# servox6-2sch.net
KiCad netlist of a schematic drawn in EAGLE
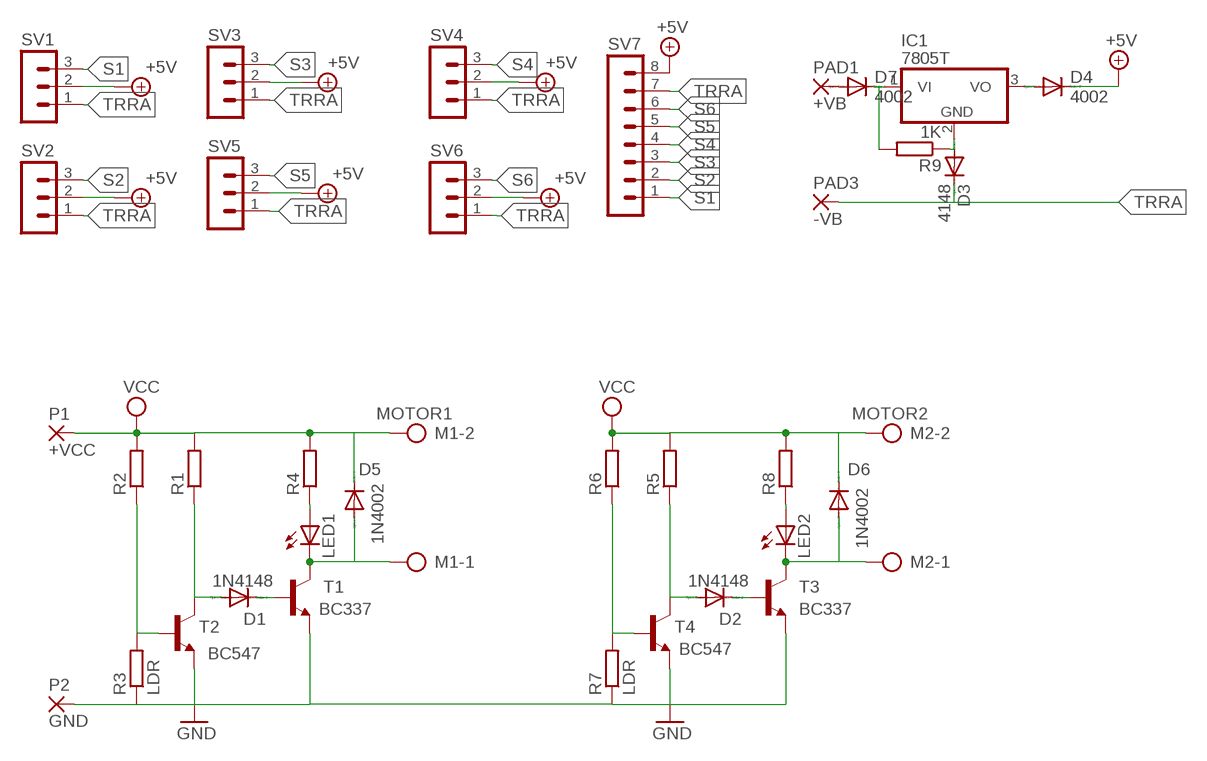
[diagram p0: schematic, sheet 1]

(export (version "E")
  (design (tool "Eeschema 10.0.6"))
  (components
    (comp (ref "D1")
      (value "1N4148")
      (footprint "eagle-import:DO35-7")
      (libsource (lib "eagle-import") (part "1N4148DO35-7"))
    )
    (comp (ref "D2")
      (value "1N4148")
      (footprint "eagle-import:DO35-7")
      (libsource (lib "eagle-import") (part "1N4148DO35-7"))
    )
    (comp (ref "D3")
      (value "4148")
      (footprint "eagle-import:DO35-7")
      (libsource (lib "eagle-import") (part "1N4148DO35-7"))
    )
    (comp (ref "D4")
      (value "4002")
      (footprint "eagle-import:DO35-7")
      (libsource (lib "eagle-import") (part "1N4148DO35-7"))
    )
    (comp (ref "D5")
      (value "1N4002")
      (footprint "eagle-import:DO41-10")
      (libsource (lib "eagle-import") (part "1N4933"))
    )
    (comp (ref "D6")
      (value "1N4002")
      (footprint "eagle-import:DO41-10")
      (libsource (lib "eagle-import") (part "1N4933"))
    )
    (comp (ref "D7")
      (value "4002")
      (footprint "eagle-import:DO35-7")
      (libsource (lib "eagle-import") (part "1N4148DO35-7"))
    )
    (comp (ref "IC1")
      (value "7805T")
      (footprint "eagle-import:TO220H")
      (libsource (lib "eagle-import") (part "78T05"))
    )
    (comp (ref "LED1")
      (value "LED3MM")
      (footprint "eagle-import:LED3MM")
      (libsource (lib "eagle-import") (part "LED3MM"))
    )
    (comp (ref "LED2")
      (value "LED3MM")
      (footprint "eagle-import:LED3MM")
      (libsource (lib "eagle-import") (part "LED3MM"))
    )
    (comp (ref "M1")
      (value "MOTOR1")
      (footprint "eagle-import:AK500_2")
      (libsource (lib "eagle-import") (part "AK500/2"))
    )
    (comp (ref "M2")
      (value "MOTOR2")
      (footprint "eagle-import:AK500_2")
      (libsource (lib "eagle-import") (part "AK500/2"))
    )
    (comp (ref "P1")
      (value "+VCC")
      (footprint "eagle-import:2,15_1,0")
      (libsource (lib "eagle-import") (part "WIREPAD2,15/1,0"))
    )
    (comp (ref "P2")
      (value "GND")
      (footprint "eagle-import:2,15_1,0")
      (libsource (lib "eagle-import") (part "WIREPAD2,15/1,0"))
    )
    (comp (ref "PAD1")
      (value "+VB")
      (footprint "eagle-import:1,6_0,9")
      (libsource (lib "eagle-import") (part "WIREPAD1,6/0,9"))
    )
    (comp (ref "PAD3")
      (value "-VB")
      (footprint "eagle-import:1,6_0,9")
      (libsource (lib "eagle-import") (part "WIREPAD1,6/0,9"))
    )
    (comp (ref "R1")
      (value "R-EU_0207/7")
      (footprint "eagle-import:0207_7")
      (libsource (lib "eagle-import") (part "R-EU_0207/7"))
    )
    (comp (ref "R2")
      (value "R-EU_0207/7")
      (footprint "eagle-import:0207_7")
      (libsource (lib "eagle-import") (part "R-EU_0207/7"))
    )
    (comp (ref "R3")
      (value "LDR")
      (footprint "eagle-import:0204_5")
      (libsource (lib "eagle-import") (part "R-EU_0204/5"))
    )
    (comp (ref "R4")
      (value "R-EU_0207/7")
      (footprint "eagle-import:0207_7")
      (libsource (lib "eagle-import") (part "R-EU_0207/7"))
    )
    (comp (ref "R5")
      (value "R-EU_0207/7")
      (footprint "eagle-import:0207_7")
      (libsource (lib "eagle-import") (part "R-EU_0207/7"))
    )
    (comp (ref "R6")
      (value "R-EU_0207/7")
      (footprint "eagle-import:0207_7")
      (libsource (lib "eagle-import") (part "R-EU_0207/7"))
    )
    (comp (ref "R7")
      (value "LDR")
      (footprint "eagle-import:0204_5")
      (libsource (lib "eagle-import") (part "R-EU_0204/5"))
    )
    (comp (ref "R8")
      (value "R-EU_0207/7")
      (footprint "eagle-import:0207_7")
      (libsource (lib "eagle-import") (part "R-EU_0207/7"))
    )
    (comp (ref "R9")
      (value "1K")
      (footprint "eagle-import:0207_7")
      (libsource (lib "eagle-import") (part "R-EU_0207/7"))
    )
    (comp (ref "SV1")
      (value "MA03-1")
      (footprint "eagle-import:MA03-1")
      (libsource (lib "eagle-import") (part "MA03-1"))
    )
    (comp (ref "SV2")
      (value "MA03-1")
      (footprint "eagle-import:MA03-1")
      (libsource (lib "eagle-import") (part "MA03-1"))
    )
    (comp (ref "SV3")
      (value "MA03-1")
      (footprint "eagle-import:MA03-1")
      (libsource (lib "eagle-import") (part "MA03-1"))
    )
    (comp (ref "SV4")
      (value "MA03-1")
      (footprint "eagle-import:MA03-1")
      (libsource (lib "eagle-import") (part "MA03-1"))
    )
    (comp (ref "SV5")
      (value "MA03-1")
      (footprint "eagle-import:MA03-1")
      (libsource (lib "eagle-import") (part "MA03-1"))
    )
    (comp (ref "SV6")
      (value "MA03-1")
      (footprint "eagle-import:MA03-1")
      (libsource (lib "eagle-import") (part "MA03-1"))
    )
    (comp (ref "SV7")
      (value "MA08-1")
      (footprint "eagle-import:MA08-1")
      (libsource (lib "eagle-import") (part "MA08-1"))
    )
    (comp (ref "T1")
      (value "BC337")
      (footprint "eagle-import:TO92-CBE")
      (libsource (lib "eagle-import") (part "-NPN-TO92-CBEBC337-25"))
    )
    (comp (ref "T2")
      (value "BC547")
      (footprint "eagle-import:TO92-CBE")
      (libsource (lib "eagle-import") (part "-NPN-TO92-CBEBC547"))
    )
    (comp (ref "T3")
      (value "BC337")
      (footprint "eagle-import:TO92-CBE")
      (libsource (lib "eagle-import") (part "-NPN-TO92-CBEBC337-25"))
    )
    (comp (ref "T4")
      (value "BC547")
      (footprint "eagle-import:TO92-CBE")
      (libsource (lib "eagle-import") (part "-NPN-TO92-CBEBC547"))
    )
  )
  (nets
    (net (code "1") (name "+5V") (class "Default")
      (node (ref "D4") (pin "C") (pinfunction "C_C") (pintype "passive"))
      (node (ref "SV1") (pin "2") (pinfunction "2_2") (pintype "passive"))
      (node (ref "SV2") (pin "2") (pinfunction "2_2") (pintype "passive"))
      (node (ref "SV3") (pin "2") (pinfunction "2_2") (pintype "passive"))
      (node (ref "SV4") (pin "2") (pinfunction "2_2") (pintype "passive"))
      (node (ref "SV5") (pin "2") (pinfunction "2_2") (pintype "passive"))
      (node (ref "SV6") (pin "2") (pinfunction "2_2") (pintype "passive"))
      (node (ref "SV7") (pin "8") (pinfunction "8_8") (pintype "passive"))
    )
    (net (code "2") (name "GND") (class "Default")
      (node (ref "P2") (pin "1") (pinfunction "P_1") (pintype "passive"))
      (node (ref "R3") (pin "1") (pinfunction "1_1") (pintype "passive"))
      (node (ref "R7") (pin "1") (pinfunction "1_1") (pintype "passive"))
      (node (ref "T1") (pin "E") (pinfunction "E_E") (pintype "passive"))
      (node (ref "T2") (pin "E") (pinfunction "E_E") (pintype "passive"))
      (node (ref "T3") (pin "E") (pinfunction "E_E") (pintype "passive"))
      (node (ref "T4") (pin "E") (pinfunction "E_E") (pintype "passive"))
    )
    (net (code "3") (name "Net-(D1-PadA)") (class "Default")
      (node (ref "D1") (pin "A") (pinfunction "A_A") (pintype "passive"))
      (node (ref "R1") (pin "1") (pinfunction "1_1") (pintype "passive"))
      (node (ref "T2") (pin "C") (pinfunction "C_C") (pintype "passive"))
    )
    (net (code "4") (name "Net-(D1-PadC)") (class "Default")
      (node (ref "D1") (pin "C") (pinfunction "C_C") (pintype "passive"))
      (node (ref "T1") (pin "B") (pinfunction "B_B") (pintype "passive"))
    )
    (net (code "5") (name "Net-(D2-PadA)") (class "Default")
      (node (ref "D2") (pin "A") (pinfunction "A_A") (pintype "passive"))
      (node (ref "R5") (pin "1") (pinfunction "1_1") (pintype "passive"))
      (node (ref "T4") (pin "C") (pinfunction "C_C") (pintype "passive"))
    )
    (net (code "6") (name "Net-(D2-PadC)") (class "Default")
      (node (ref "D2") (pin "C") (pinfunction "C_C") (pintype "passive"))
      (node (ref "T3") (pin "B") (pinfunction "B_B") (pintype "passive"))
    )
    (net (code "7") (name "Net-(IC1-GND)") (class "Default")
      (node (ref "D3") (pin "A") (pinfunction "A_A") (pintype "passive"))
      (node (ref "IC1") (pin "2") (pinfunction "GND_2") (pintype "passive"))
      (node (ref "R9") (pin "1") (pinfunction "1_1") (pintype "passive"))
    )
    (net (code "8") (name "Net-(IC1-VI)") (class "Default")
      (node (ref "D7") (pin "C") (pinfunction "C_C") (pintype "passive"))
      (node (ref "IC1") (pin "1") (pinfunction "VI_1") (pintype "input"))
      (node (ref "R9") (pin "2") (pinfunction "2_2") (pintype "passive"))
    )
    (net (code "9") (name "Net-(IC1-VO)") (class "Default")
      (node (ref "D4") (pin "A") (pinfunction "A_A") (pintype "passive"))
      (node (ref "IC1") (pin "3") (pinfunction "VO_3") (pintype "passive"))
    )
    (net (code "10") (name "Net-(LED1-C)") (class "Default")
      (node (ref "D5") (pin "A") (pinfunction "A_A") (pintype "passive"))
      (node (ref "LED1") (pin "K") (pinfunction "C_K") (pintype "passive"))
      (node (ref "M1") (pin "1") (pinfunction "KL_1") (pintype "passive"))
      (node (ref "T1") (pin "C") (pinfunction "C_C") (pintype "passive"))
    )
    (net (code "11") (name "Net-(LED1-PadA)") (class "Default")
      (node (ref "LED1") (pin "A") (pinfunction "A_A") (pintype "passive"))
      (node (ref "R4") (pin "1") (pinfunction "1_1") (pintype "passive"))
    )
    (net (code "12") (name "Net-(LED2-C)") (class "Default")
      (node (ref "D6") (pin "A") (pinfunction "A_A") (pintype "passive"))
      (node (ref "LED2") (pin "K") (pinfunction "C_K") (pintype "passive"))
      (node (ref "M2") (pin "1") (pinfunction "KL_1") (pintype "passive"))
      (node (ref "T3") (pin "C") (pinfunction "C_C") (pintype "passive"))
    )
    (net (code "13") (name "Net-(LED2-PadA)") (class "Default")
      (node (ref "LED2") (pin "A") (pinfunction "A_A") (pintype "passive"))
      (node (ref "R8") (pin "1") (pinfunction "1_1") (pintype "passive"))
    )
    (net (code "14") (name "Net-(PAD1-P)") (class "Default")
      (node (ref "D7") (pin "A") (pinfunction "A_A") (pintype "passive"))
      (node (ref "PAD1") (pin "1") (pinfunction "P_1") (pintype "passive"))
    )
    (net (code "15") (name "Net-(R2-Pad1)") (class "Default")
      (node (ref "R2") (pin "1") (pinfunction "1_1") (pintype "passive"))
      (node (ref "R3") (pin "2") (pinfunction "2_2") (pintype "passive"))
      (node (ref "T2") (pin "B") (pinfunction "B_B") (pintype "passive"))
    )
    (net (code "16") (name "Net-(R6-Pad1)") (class "Default")
      (node (ref "R6") (pin "1") (pinfunction "1_1") (pintype "passive"))
      (node (ref "R7") (pin "2") (pinfunction "2_2") (pintype "passive"))
      (node (ref "T4") (pin "B") (pinfunction "B_B") (pintype "passive"))
    )
    (net (code "17") (name "S1") (class "Default")
      (node (ref "SV1") (pin "3") (pinfunction "3_3") (pintype "passive"))
      (node (ref "SV7") (pin "1") (pinfunction "1_1") (pintype "passive"))
    )
    (net (code "18") (name "S2") (class "Default")
      (node (ref "SV2") (pin "3") (pinfunction "3_3") (pintype "passive"))
      (node (ref "SV7") (pin "2") (pinfunction "2_2") (pintype "passive"))
    )
    (net (code "19") (name "S3") (class "Default")
      (node (ref "SV3") (pin "3") (pinfunction "3_3") (pintype "passive"))
      (node (ref "SV7") (pin "3") (pinfunction "3_3") (pintype "passive"))
    )
    (net (code "20") (name "S4") (class "Default")
      (node (ref "SV4") (pin "3") (pinfunction "3_3") (pintype "passive"))
      (node (ref "SV7") (pin "4") (pinfunction "4_4") (pintype "passive"))
    )
    (net (code "21") (name "S5") (class "Default")
      (node (ref "SV5") (pin "3") (pinfunction "3_3") (pintype "passive"))
      (node (ref "SV7") (pin "5") (pinfunction "5_5") (pintype "passive"))
    )
    (net (code "22") (name "S6") (class "Default")
      (node (ref "SV6") (pin "3") (pinfunction "3_3") (pintype "passive"))
      (node (ref "SV7") (pin "6") (pinfunction "6_6") (pintype "passive"))
    )
    (net (code "23") (name "TRRA") (class "Default")
      (node (ref "D3") (pin "C") (pinfunction "C_C") (pintype "passive"))
      (node (ref "PAD3") (pin "1") (pinfunction "P_1") (pintype "passive"))
      (node (ref "SV1") (pin "1") (pinfunction "1_1") (pintype "passive"))
      (node (ref "SV2") (pin "1") (pinfunction "1_1") (pintype "passive"))
      (node (ref "SV3") (pin "1") (pinfunction "1_1") (pintype "passive"))
      (node (ref "SV4") (pin "1") (pinfunction "1_1") (pintype "passive"))
      (node (ref "SV5") (pin "1") (pinfunction "1_1") (pintype "passive"))
      (node (ref "SV6") (pin "1") (pinfunction "1_1") (pintype "passive"))
      (node (ref "SV7") (pin "7") (pinfunction "7_7") (pintype "passive"))
    )
    (net (code "24") (name "VCC") (class "Default")
      (node (ref "D5") (pin "C") (pinfunction "C_C") (pintype "passive"))
      (node (ref "D6") (pin "C") (pinfunction "C_C") (pintype "passive"))
      (node (ref "M1") (pin "2") (pinfunction "KL_2") (pintype "passive"))
      (node (ref "M2") (pin "2") (pinfunction "KL_2") (pintype "passive"))
      (node (ref "P1") (pin "1") (pinfunction "P_1") (pintype "passive"))
      (node (ref "R1") (pin "2") (pinfunction "2_2") (pintype "passive"))
      (node (ref "R2") (pin "2") (pinfunction "2_2") (pintype "passive"))
      (node (ref "R4") (pin "2") (pinfunction "2_2") (pintype "passive"))
      (node (ref "R5") (pin "2") (pinfunction "2_2") (pintype "passive"))
      (node (ref "R6") (pin "2") (pinfunction "2_2") (pintype "passive"))
      (node (ref "R8") (pin "2") (pinfunction "2_2") (pintype "passive"))
    )
  )
)
